# Power_Supply.net
KiCad netlist of a schematic drawn in Altium Designer
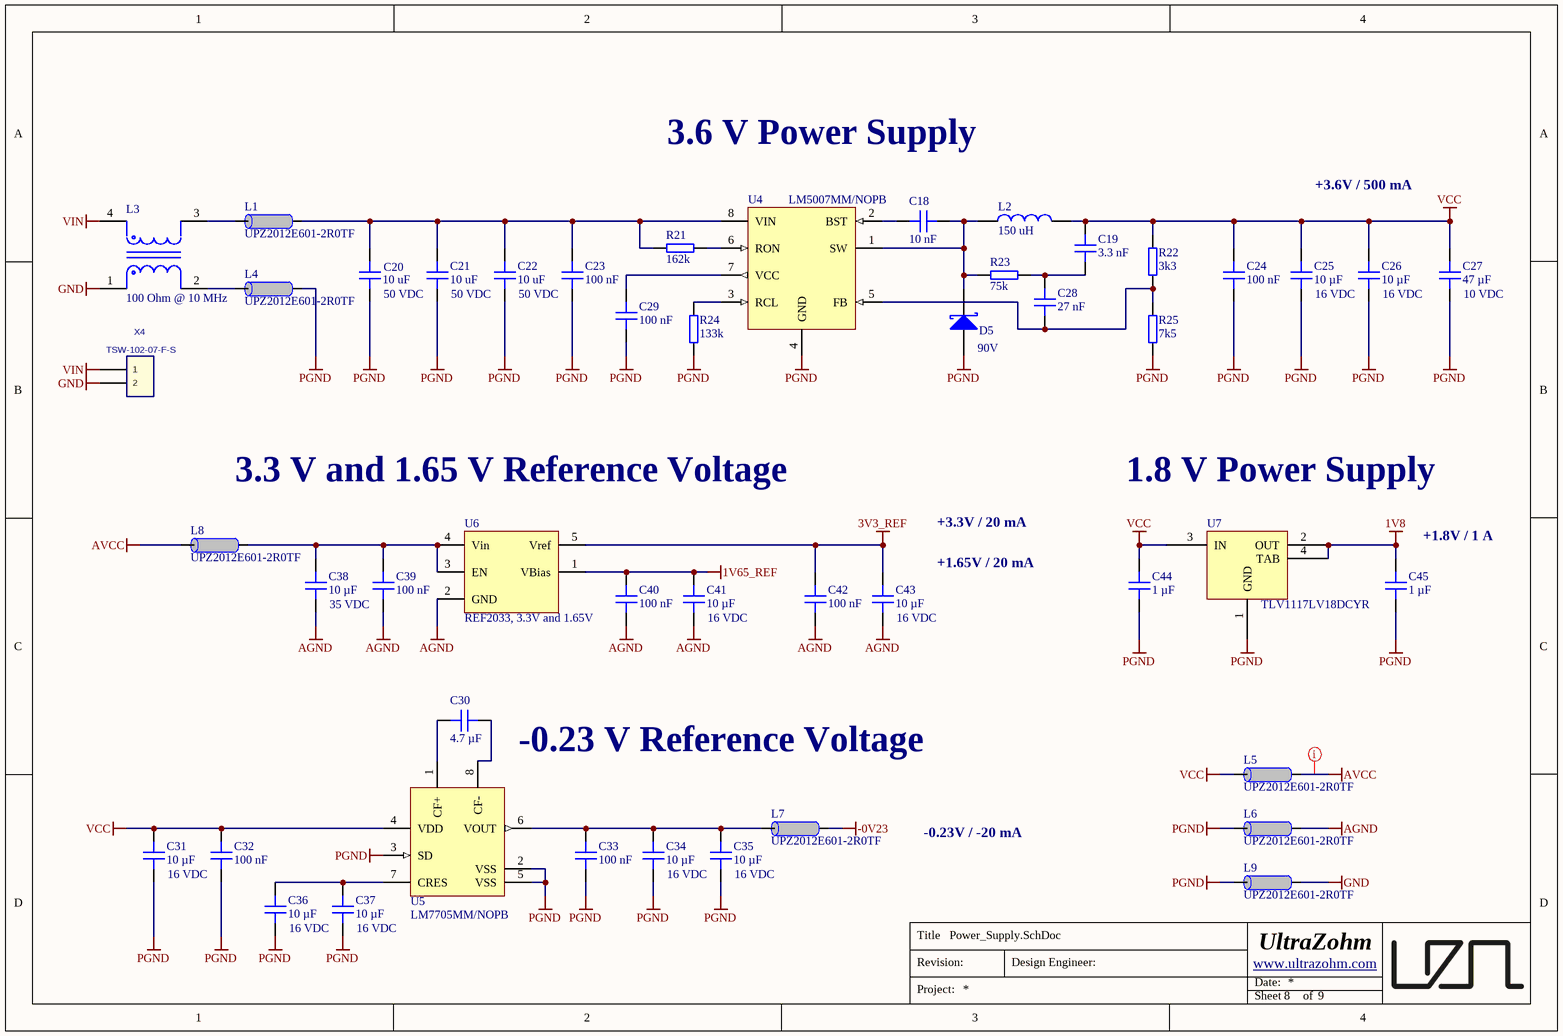
[diagram p0: Power_Supply.SchDoc]

(export (version "E")
  (design (tool "Eeschema 10.0.6"))
  (components
    (comp (ref "C18")
      (value "10 nF")
      (footprint "C_0603")
      (description "50V 10nF X7R ±10% 0603  Multilayer Ceramic Capacitors MLCC - SMD/SMT ROHS")
      (fields
        (field (name "MANUFACTURER PART NUMBER") "0603B103K500NT")
        (field (name "MANUFACTURER") "FH (Guangdong Fenghua Advanced Tech)")
        (field (name "CREATED FROM") "AGeiger")
      )
      (libsource (lib "user") (part "Capacitor"))
    )
    (comp (ref "C19")
      (value "3.3 nF")
      (footprint "C_0603")
      (description "50V 3.3nF X7R ±10% 0603  Multilayer Ceramic Capacitors MLCC - SMD/SMT ROHS")
      (fields
        (field (name "MANUFACTURER PART NUMBER") "CL10B332KB8NNNC")
        (field (name "MANUFACTURER") "Samsung Electro-Mechanics")
        (field (name "CREATED FROM") "AGeiger")
      )
      (libsource (lib "user") (part "Capacitor"))
    )
    (comp (ref "C20")
      (value "10 uF")
      (footprint "C_1206")
      (description "50V 10uF X7R ±10% 1206  Multilayer Ceramic Capacitors MLCC - SMD/SMT ROHS")
      (fields
        (field (name "MANUFACTURER PART NUMBER") "CL31B106KBHNNNE")
        (field (name "MANUFACTURER") "Samsung Electro-Mechanics")
        (field (name "VOLTAGE RATING") "50 VDC")
        (field (name "CREATED FROM") "AGeiger")
      )
      (libsource (lib "user") (part "Capacitor"))
    )
    (comp (ref "C21")
      (value "10 uF")
      (footprint "C_1206")
      (description "50V 10uF X7R ±10% 1206  Multilayer Ceramic Capacitors MLCC - SMD/SMT ROHS")
      (fields
        (field (name "MANUFACTURER PART NUMBER") "CL31B106KBHNNNE")
        (field (name "MANUFACTURER") "Samsung Electro-Mechanics")
        (field (name "VOLTAGE RATING") "50 VDC")
        (field (name "CREATED FROM") "AGeiger")
      )
      (libsource (lib "user") (part "Capacitor"))
    )
    (comp (ref "C22")
      (value "10 uF")
      (footprint "C_1206")
      (description "50V 10uF X7R ±10% 1206  Multilayer Ceramic Capacitors MLCC - SMD/SMT ROHS")
      (fields
        (field (name "MANUFACTURER PART NUMBER") "CL31B106KBHNNNE")
        (field (name "MANUFACTURER") "Samsung Electro-Mechanics")
        (field (name "VOLTAGE RATING") "50 VDC")
        (field (name "CREATED FROM") "AGeiger")
      )
      (libsource (lib "user") (part "Capacitor"))
    )
    (comp (ref "C23")
      (value "100 nF")
      (footprint "C_0603")
      (description "Capacitor 0603, 50 VDC, 100 nF, X7R")
      (fields
        (field (name "MANUFACTURER PART NUMBER") "CC0603KRX7R9BB104")
        (field (name "MANUFACTURER") "YAGEO")
        (field (name "CREATED FROM") "AGeiger")
      )
      (libsource (lib "user") (part "Capacitor"))
    )
    (comp (ref "C24")
      (value "100 nF")
      (footprint "C_0603")
      (description "Capacitor 0603, 50 VDC, 100 nF, X7R")
      (fields
        (field (name "MANUFACTURER PART NUMBER") "CC0603KRX7R9BB104")
        (field (name "MANUFACTURER") "YAGEO")
        (field (name "CREATED FROM") "AGeiger")
      )
      (libsource (lib "user") (part "Capacitor"))
    )
    (comp (ref "C25")
      (value "10 µF")
      (footprint "C_0603")
      (description "Capacitor 0603, 16 VDC, 10 µF, X5R")
      (fields
        (field (name "MANUFACTURER PART NUMBER") "CL10A106MO8NQNC")
        (field (name "MANUFACTURER") "Samsung Electro-Mechanics")
        (field (name "VOLTAGE RATING") "16 VDC")
        (field (name "CREATED FROM") "AGeiger")
      )
      (libsource (lib "user") (part "Capacitor"))
    )
    (comp (ref "C26")
      (value "10 µF")
      (footprint "C_0603")
      (description "Capacitor 0603, 16 VDC, 10 µF, X5R")
      (fields
        (field (name "MANUFACTURER PART NUMBER") "CL10A106MO8NQNC")
        (field (name "MANUFACTURER") "Samsung Electro-Mechanics")
        (field (name "VOLTAGE RATING") "16 VDC")
        (field (name "CREATED FROM") "AGeiger")
      )
      (libsource (lib "user") (part "Capacitor"))
    )
    (comp (ref "C27")
      (value "47 µF")
      (footprint "C_1210_N")
      (description "10V 47uF X7R ±10% 1210  Multilayer Ceramic Capacitors MLCC - SMD/SMT ROHS")
      (fields
        (field (name "MANUFACTURER PART NUMBER") "GRM32ER71A476KE15L")
        (field (name "MANUFACTURER") "Murata Electronics")
        (field (name "VOLTAGE RATING") "10 VDC")
        (field (name "CREATED FROM") "AGeiger")
      )
      (libsource (lib "user") (part "Capacitor"))
    )
    (comp (ref "C28")
      (value "27 nF")
      (footprint "C_0603")
      (description "50V 27nF X7R ±10% 0603  Multilayer Ceramic Capacitors MLCC - SMD/SMT ROHS")
      (fields
        (field (name "MANUFACTURER PART NUMBER") "CC0603KRX7R9BB273")
        (field (name "MANUFACTURER") "YAGEO")
        (field (name "CREATED FROM") "AGeiger")
      )
      (libsource (lib "user") (part "Capacitor"))
    )
    (comp (ref "C29")
      (value "100 nF")
      (footprint "C_0603")
      (description "Capacitor 0603, 50 VDC, 100 nF, X7R")
      (fields
        (field (name "MANUFACTURER PART NUMBER") "CC0603KRX7R9BB104")
        (field (name "MANUFACTURER") "YAGEO")
        (field (name "CREATED FROM") "AGeiger")
      )
      (libsource (lib "user") (part "Capacitor"))
    )
    (comp (ref "C30")
      (value "4.7 µF")
      (footprint "C_0805")
      (description "25V 4.7uF X5R ±10% 0805  Multilayer Ceramic Capacitors MLCC - SMD/SMT ROHS")
      (fields
        (field (name "MANUFACTURER PART NUMBER") "CL21A475KAQNNNE")
        (field (name "MANUFACTURER") "Samsung Electro-Mechanics")
        (field (name "CREATED FROM") "AGeiger")
      )
      (libsource (lib "user") (part "Capacitor"))
    )
    (comp (ref "C31")
      (value "10 µF")
      (footprint "C_0603")
      (description "Capacitor 0603, 16 VDC, 10 µF, X5R")
      (fields
        (field (name "MANUFACTURER PART NUMBER") "CL10A106MO8NQNC")
        (field (name "MANUFACTURER") "Samsung Electro-Mechanics")
        (field (name "VOLTAGE RATING") "16 VDC")
        (field (name "CREATED FROM") "AGeiger")
      )
      (libsource (lib "user") (part "Capacitor"))
    )
    (comp (ref "C32")
      (value "100 nF")
      (footprint "C_0603")
      (description "Capacitor 0603, 50 VDC, 100 nF, X7R")
      (fields
        (field (name "MANUFACTURER PART NUMBER") "CC0603KRX7R9BB104")
        (field (name "MANUFACTURER") "YAGEO")
        (field (name "CREATED FROM") "AGeiger")
      )
      (libsource (lib "user") (part "Capacitor"))
    )
    (comp (ref "C33")
      (value "100 nF")
      (footprint "C_0603")
      (description "Capacitor 0603, 50 VDC, 100 nF, X7R")
      (fields
        (field (name "MANUFACTURER PART NUMBER") "CC0603KRX7R9BB104")
        (field (name "MANUFACTURER") "YAGEO")
        (field (name "CREATED FROM") "AGeiger")
      )
      (libsource (lib "user") (part "Capacitor"))
    )
    (comp (ref "C34")
      (value "10 µF")
      (footprint "C_0603")
      (description "Capacitor 0603, 16 VDC, 10 µF, X5R")
      (fields
        (field (name "MANUFACTURER PART NUMBER") "CL10A106MO8NQNC")
        (field (name "MANUFACTURER") "Samsung Electro-Mechanics")
        (field (name "VOLTAGE RATING") "16 VDC")
        (field (name "CREATED FROM") "AGeiger")
      )
      (libsource (lib "user") (part "Capacitor"))
    )
    (comp (ref "C35")
      (value "10 µF")
      (footprint "C_0603")
      (description "Capacitor 0603, 16 VDC, 10 µF, X5R")
      (fields
        (field (name "MANUFACTURER PART NUMBER") "CL10A106MO8NQNC")
        (field (name "MANUFACTURER") "Samsung Electro-Mechanics")
        (field (name "VOLTAGE RATING") "16 VDC")
        (field (name "CREATED FROM") "AGeiger")
      )
      (libsource (lib "user") (part "Capacitor"))
    )
    (comp (ref "C36")
      (value "10 µF")
      (footprint "C_0603")
      (description "Capacitor 0603, 16 VDC, 10 µF, X5R")
      (fields
        (field (name "MANUFACTURER PART NUMBER") "CL10A106MO8NQNC")
        (field (name "MANUFACTURER") "Samsung Electro-Mechanics")
        (field (name "VOLTAGE RATING") "16 VDC")
        (field (name "CREATED FROM") "AGeiger")
      )
      (libsource (lib "user") (part "Capacitor"))
    )
    (comp (ref "C37")
      (value "10 µF")
      (footprint "C_0603")
      (description "Capacitor 0603, 16 VDC, 10 µF, X5R")
      (fields
        (field (name "MANUFACTURER PART NUMBER") "CL10A106MO8NQNC")
        (field (name "MANUFACTURER") "Samsung Electro-Mechanics")
        (field (name "VOLTAGE RATING") "16 VDC")
        (field (name "CREATED FROM") "AGeiger")
      )
      (libsource (lib "user") (part "Capacitor"))
    )
    (comp (ref "C38")
      (value "10 µF")
      (footprint "CAPC_0805_L")
      (description "Capacitor 0805, 35 VDC, 10 µF, X5R")
      (fields
        (field (name "MANUFACTURER PART NUMBER") "GRM21BR6YA106KE43L")
        (field (name "MANUFACTURER") "Murata Electronics")
        (field (name "VOLTAGE RATING") "35 VDC")
        (field (name "CREATED FROM") "AGeiger")
      )
      (libsource (lib "user") (part "Capacitor"))
    )
    (comp (ref "C39")
      (value "100 nF")
      (footprint "C_0603")
      (description "Capacitor 0603, 50 VDC, 100 nF, X7R")
      (fields
        (field (name "MANUFACTURER PART NUMBER") "CC0603KRX7R9BB104")
        (field (name "MANUFACTURER") "YAGEO")
        (field (name "CREATED FROM") "AGeiger")
      )
      (libsource (lib "user") (part "Capacitor"))
    )
    (comp (ref "C40")
      (value "100 nF")
      (footprint "C_0603")
      (description "Capacitor 0603, 50 VDC, 100 nF, X7R")
      (fields
        (field (name "MANUFACTURER PART NUMBER") "CC0603KRX7R9BB104")
        (field (name "MANUFACTURER") "YAGEO")
        (field (name "CREATED FROM") "AGeiger")
      )
      (libsource (lib "user") (part "Capacitor"))
    )
    (comp (ref "C41")
      (value "10 µF")
      (footprint "C_0603")
      (description "Capacitor 0603, 16 VDC, 10 µF, X5R")
      (fields
        (field (name "MANUFACTURER PART NUMBER") "CL10A106MO8NQNC")
        (field (name "MANUFACTURER") "Samsung Electro-Mechanics")
        (field (name "VOLTAGE RATING") "16 VDC")
        (field (name "CREATED FROM") "AGeiger")
      )
      (libsource (lib "user") (part "Capacitor"))
    )
    (comp (ref "C42")
      (value "100 nF")
      (footprint "C_0603")
      (description "Capacitor 0603, 50 VDC, 100 nF, X7R")
      (fields
        (field (name "MANUFACTURER PART NUMBER") "CC0603KRX7R9BB104")
        (field (name "MANUFACTURER") "YAGEO")
        (field (name "CREATED FROM") "AGeiger")
      )
      (libsource (lib "user") (part "Capacitor"))
    )
    (comp (ref "C43")
      (value "10 µF")
      (footprint "C_0603")
      (description "Capacitor 0603, 16 VDC, 10 µF, X5R")
      (fields
        (field (name "MANUFACTURER PART NUMBER") "CL10A106MO8NQNC")
        (field (name "MANUFACTURER") "Samsung Electro-Mechanics")
        (field (name "VOLTAGE RATING") "16 VDC")
        (field (name "CREATED FROM") "AGeiger")
      )
      (libsource (lib "user") (part "Capacitor"))
    )
    (comp (ref "C44")
      (value "1 µF")
      (footprint "C_0603")
      (description "50V 1uF X7R ±10% 0603 Multilayer Ceramic Capacitors MLCC - SMD/SMT ROHS")
      (fields
        (field (name "MANUFACTURER PART NUMBER") "UMK107AB7105KA-T")
        (field (name "MANUFACTURER") "Taiyo Yuden")
        (field (name "CREATED FROM") "NDiringer")
      )
      (libsource (lib "user") (part "Capacitor"))
    )
    (comp (ref "C45")
      (value "1 µF")
      (footprint "C_0603")
      (description "50V 1uF X7R ±10% 0603 Multilayer Ceramic Capacitors MLCC - SMD/SMT ROHS")
      (fields
        (field (name "MANUFACTURER PART NUMBER") "UMK107AB7105KA-T")
        (field (name "MANUFACTURER") "Taiyo Yuden")
        (field (name "CREATED FROM") "NDiringer")
      )
      (libsource (lib "user") (part "Capacitor"))
    )
    (comp (ref "D5")
      (value "90V")
      (footprint "DIOM5226X262N")
      (description "Schottky Diode, 90 V, 3 A")
      (fields
        (field (name "MF") "Vishay")
        (field (name "MPN") "BYS12-90-E3/TR3")
        (field (name "CREATED FROM") "AGeiger")
      )
      (libsource (lib "user") (part "BYS12-90"))
    )
    (comp (ref "L1")
      (value "UPZ2012E601-2R0TF")
      (footprint "INDC2012X92N_V")
      (description "2A 1 90mΩ 600Ω@100MHz ±25% 0805  Ferrite Beads ROHS")
      (fields
        (field (name "MANUFACTURER") "Sunlord")
        (field (name "LCSC PART NUMBER") "C98308")
        (field (name "CREATED FROM") "AGeiger")
      )
      (libsource (lib "user") (part "Ferrite_Bead"))
    )
    (comp (ref "L2")
      (value "150 uH")
      (footprint "POWER_INDUCTOR_8040")
      (description "850mA 150uH ±20% 410mΩ SMD  Power Inductors ROHS")
      (fields
        (field (name "MF") "EPCOS / TDK")
        (field (name "MPN") "B82464G4154M")
        (field (name "CREATED FROM") "AGeiger")
      )
      (libsource (lib "user") (part "B82464G4154M"))
    )
    (comp (ref "L3")
      (value "100 Ohm @ 10 MHz")
      (footprint "FP-DLW5BT-MFG")
      (description "-40℃~125℃ 1.5A 56mΩ 50V 100Ω @ 10MHz 125VDC SMD,5x5mm Common Mode Filters ROHS")
      (fields
        (field (name "MANUFACTURER PART NUMBER") "DLW5BTH142TQ2L")
        (field (name "MANUFACTURER") "Murata")
        (field (name "CREATED FROM") "AGeiger")
      )
      (libsource (lib "user") (part "Common_Mode_Filter"))
    )
    (comp (ref "L4")
      (value "UPZ2012E601-2R0TF")
      (footprint "INDC2012X92N_V")
      (description "2A 1 90mΩ 600Ω@100MHz ±25% 0805  Ferrite Beads ROHS")
      (fields
        (field (name "MANUFACTURER") "Sunlord")
        (field (name "LCSC PART NUMBER") "C98308")
        (field (name "CREATED FROM") "AGeiger")
      )
      (libsource (lib "user") (part "Ferrite_Bead"))
    )
    (comp (ref "L5")
      (value "UPZ2012E601-2R0TF")
      (footprint "INDC2012X92N_V")
      (description "2A 1 90mΩ 600Ω@100MHz ±25% 0805  Ferrite Beads ROHS")
      (fields
        (field (name "MANUFACTURER") "Sunlord")
        (field (name "LCSC PART NUMBER") "C98308")
        (field (name "CREATED FROM") "AGeiger")
      )
      (libsource (lib "user") (part "Ferrite_Bead"))
    )
    (comp (ref "L6")
      (value "UPZ2012E601-2R0TF")
      (footprint "INDC2012X92N_V")
      (description "2A 1 90mΩ 600Ω@100MHz ±25% 0805  Ferrite Beads ROHS")
      (fields
        (field (name "MANUFACTURER") "Sunlord")
        (field (name "LCSC PART NUMBER") "C98308")
        (field (name "CREATED FROM") "AGeiger")
      )
      (libsource (lib "user") (part "Ferrite_Bead"))
    )
    (comp (ref "L7")
      (value "UPZ2012E601-2R0TF")
      (footprint "INDC2012X92N_V")
      (description "2A 1 90mΩ 600Ω@100MHz ±25% 0805  Ferrite Beads ROHS")
      (fields
        (field (name "MANUFACTURER") "Sunlord")
        (field (name "LCSC PART NUMBER") "C98308")
        (field (name "CREATED FROM") "AGeiger")
      )
      (libsource (lib "user") (part "Ferrite_Bead"))
    )
    (comp (ref "L8")
      (value "UPZ2012E601-2R0TF")
      (footprint "INDC2012X92N_V")
      (description "2A 1 90mΩ 600Ω@100MHz ±25% 0805  Ferrite Beads ROHS")
      (fields
        (field (name "MANUFACTURER") "Sunlord")
        (field (name "LCSC PART NUMBER") "C98308")
        (field (name "CREATED FROM") "AGeiger")
      )
      (libsource (lib "user") (part "Ferrite_Bead"))
    )
    (comp (ref "L9")
      (value "UPZ2012E601-2R0TF")
      (footprint "INDC2012X92N_V")
      (description "2A 1 90mΩ 600Ω@100MHz ±25% 0805  Ferrite Beads ROHS")
      (fields
        (field (name "MANUFACTURER") "Sunlord")
        (field (name "LCSC PART NUMBER") "C98308")
        (field (name "CREATED FROM") "AGeiger")
      )
      (libsource (lib "user") (part "Ferrite_Bead"))
    )
    (comp (ref "R21")
      (value "162k")
      (footprint "RES 0603_1608")
      (fields
        (field (name "MANUFACTURER PART NUMBER") "0603WAF1623T5E")
        (field (name "MANUFACTURER") "UNI-ROYAL")
        (field (name "TOLERANCE") "1%")
        (field (name "CREATED FROM") "AGeiger")
      )
      (libsource (lib "user") (part "Resistor"))
    )
    (comp (ref "R22")
      (value "3k3")
      (footprint "RES 0603_1608")
      (fields
        (field (name "MANUFACTURER PART NUMBER") "0603WAF3301T5E")
        (field (name "MANUFACTURER") "UNI-ROYAL")
        (field (name "TOLERANCE") "1%")
        (field (name "CREATED FROM") "AGeiger")
      )
      (libsource (lib "user") (part "Resistor"))
    )
    (comp (ref "R23")
      (value "75k")
      (footprint "RES 0603_1608")
      (fields
        (field (name "MANUFACTURER PART NUMBER") "0603WAF7502T5E")
        (field (name "MANUFACTURER") "UNI-ROYAL")
        (field (name "TOLERANCE") "1%")
        (field (name "CREATED FROM") "AGeiger")
      )
      (libsource (lib "user") (part "Resistor"))
    )
    (comp (ref "R24")
      (value "133k")
      (footprint "RES 0603_1608")
      (fields
        (field (name "MANUFACTURER PART NUMBER") "AC0603FR-07133KL")
        (field (name "MANUFACTURER") "YAGEO")
        (field (name "TOLERANCE") "1%")
        (field (name "CREATED FROM") "AGeiger")
      )
      (libsource (lib "user") (part "Resistor"))
    )
    (comp (ref "R25")
      (value "7k5")
      (footprint "RES 0603_1608")
      (fields
        (field (name "MANUFACTURER PART NUMBER") "0603WAF7501T5E")
        (field (name "MANUFACTURER") "UNI-ROYAL")
        (field (name "TOLERANCE") "1%")
        (field (name "CREATED FROM") "AGeiger")
      )
      (libsource (lib "user") (part "Resistor"))
    )
    (comp (ref "U4")
      (value "LM5007MM/NOPB")
      (footprint "TSOP65P490X110-8N")
      (fields
        (field (name "MANUFACTURER") "Texas Instruments")
        (field (name "LCSC PART NUMBER") "C23920")
        (field (name "CREATED FROM") "AGeiger")
      )
      (libsource (lib "user") (part "LM5007"))
    )
    (comp (ref "U5")
      (value "LM7705MM/NOPB")
      (footprint "MSOP-8_DGK0008A_L")
      (description "Low-Noise Negative Bias Generator")
      (fields
        (field (name "MF") "Texas Instruments")
        (field (name "LCSC PART NUMBER") "C129980")
        (field (name "CREATED FROM") "AGeiger")
      )
      (libsource (lib "user") (part "LM7705"))
    )
    (comp (ref "U6")
      (value "REF2033, 3.3V and 1.65V")
      (footprint "SOT23-5_N")
      (description "REF20xx Low-Drift, Low-Power, Dual-Output, VREF and VREF / 2 Voltage References")
      (fields
        (field (name "MANUFACTURER PART NUMBER") "REF2033AIDDCT")
        (field (name "MANUFACTURER") "Texas Instruments")
        (field (name "CREATED FROM") "AGeiger")
      )
      (libsource (lib "user") (part "REF2033"))
    )
    (comp (ref "U7")
      (value "TLV1117LV18DCYR")
      (footprint "SOT230P700X170-4N")
      (description "1-A, Positive Fixed-Voltage, Low-Dropout Regulator")
      (fields
        (field (name "MF") "Texas Instruments")
        (field (name "LCSC PART NUMBER") "C80105")
        (field (name "CREATED FROM") "AGeiger")
      )
      (libsource (lib "user") (part "TLV1117LV18DCYR"))
    )
    (comp (ref "X4")
      (value "TSW-102-07-F-S")
      (footprint "TSW-102-XX-XXX-S")
      (description "Pin Header, 2.54mm, 2x1")
      (fields
        (field (name "MANUFACTURER") "SAMTEC")
        (field (name "CREATED BY") "May 18, 2016 - Wendy Xin")
        (field (name "CREATED FROM") "AGeiger")
      )
      (libsource (lib "user") (part "TSW-102-XX-XXX-S"))
    )
  )
  (nets
    (net (code "1") (name "-0V23") (class "Default")
      (node (ref "L7") (pin "1") (pinfunction "1_1") (pintype "passive"))
    )
    (net (code "2") (name "1V8") (class "Default")
      (node (ref "C45") (pin "2") (pinfunction "2_2") (pintype "passive"))
      (node (ref "U7") (pin "2") (pinfunction "OUT_2") (pintype "power_in"))
      (node (ref "U7") (pin "4") (pinfunction "TAB_4") (pintype "power_in"))
    )
    (net (code "3") (name "1V65_REF") (class "Default")
      (node (ref "C40") (pin "2") (pinfunction "2_2") (pintype "passive"))
      (node (ref "C41") (pin "2") (pinfunction "2_2") (pintype "passive"))
      (node (ref "U6") (pin "1") (pinfunction "VBias_1") (pintype "passive"))
    )
    (net (code "4") (name "3V3_REF") (class "Default")
      (node (ref "C42") (pin "2") (pinfunction "2_2") (pintype "passive"))
      (node (ref "C43") (pin "2") (pinfunction "2_2") (pintype "passive"))
      (node (ref "U6") (pin "5") (pinfunction "Vref_5") (pintype "passive"))
    )
    (net (code "5") (name "AGND") (class "Default")
      (node (ref "C38") (pin "1") (pinfunction "1_1") (pintype "passive"))
      (node (ref "C39") (pin "1") (pinfunction "1_1") (pintype "passive"))
      (node (ref "C40") (pin "1") (pinfunction "1_1") (pintype "passive"))
      (node (ref "C41") (pin "1") (pinfunction "1_1") (pintype "passive"))
      (node (ref "C42") (pin "1") (pinfunction "1_1") (pintype "passive"))
      (node (ref "C43") (pin "1") (pinfunction "1_1") (pintype "passive"))
      (node (ref "L6") (pin "1") (pinfunction "1_1") (pintype "passive"))
      (node (ref "U6") (pin "2") (pinfunction "GND_2") (pintype "passive"))
    )
    (net (code "6") (name "AVCC") (class "Default")
      (node (ref "L5") (pin "1") (pinfunction "1_1") (pintype "passive"))
      (node (ref "L8") (pin "2") (pinfunction "2_2") (pintype "passive"))
    )
    (net (code "7") (name "GND") (class "Default")
      (node (ref "L3") (pin "1") (pinfunction "1_1") (pintype "passive"))
      (node (ref "L9") (pin "1") (pinfunction "1_1") (pintype "passive"))
      (node (ref "X4") (pin "2") (pinfunction "2_2") (pintype "passive"))
    )
    (net (code "8") (name "Net-(C19-Pad1)") (class "Default")
      (node (ref "C19") (pin "1") (pinfunction "1_1") (pintype "passive"))
      (node (ref "C28") (pin "2") (pinfunction "2_2") (pintype "passive"))
      (node (ref "R23") (pin "2") (pinfunction "2_2") (pintype "passive"))
    )
    (net (code "9") (name "Net-(D5-K)") (class "Default")
      (node (ref "C18") (pin "2") (pinfunction "2_2") (pintype "passive"))
      (node (ref "D5") (pin "1") (pinfunction "K_1") (pintype "passive"))
      (node (ref "L2") (pin "1") (pinfunction "1_1") (pintype "passive"))
      (node (ref "R23") (pin "1") (pinfunction "1_1") (pintype "passive"))
      (node (ref "U4") (pin "1") (pinfunction "SW_1") (pintype "power_in"))
    )
    (net (code "10") (name "Net-(L1-Pad2)") (class "Default")
      (node (ref "L1") (pin "2") (pinfunction "2_2") (pintype "passive"))
      (node (ref "L3") (pin "3") (pinfunction "3_3") (pintype "passive"))
    )
    (net (code "11") (name "Net-(L3-Pad2)") (class "Default")
      (node (ref "L3") (pin "2") (pinfunction "2_2") (pintype "passive"))
      (node (ref "L4") (pin "2") (pinfunction "2_2") (pintype "passive"))
    )
    (net (code "12") (name "Net-(U4-BST)") (class "Default")
      (node (ref "C18") (pin "1") (pinfunction "1_1") (pintype "passive"))
      (node (ref "U4") (pin "2") (pinfunction "BST_2") (pintype "input"))
    )
    (net (code "13") (name "Net-(U4-FB)") (class "Default")
      (node (ref "C28") (pin "1") (pinfunction "1_1") (pintype "passive"))
      (node (ref "R22") (pin "1") (pinfunction "1_1") (pintype "passive"))
      (node (ref "R25") (pin "2") (pinfunction "2_2") (pintype "passive"))
      (node (ref "U4") (pin "5") (pinfunction "FB_5") (pintype "input"))
    )
    (net (code "14") (name "Net-(U4-RCL)") (class "Default")
      (node (ref "R24") (pin "2") (pinfunction "2_2") (pintype "passive"))
      (node (ref "U4") (pin "3") (pinfunction "RCL_3") (pintype "input"))
    )
    (net (code "15") (name "Net-(U4-RON)") (class "Default")
      (node (ref "R21") (pin "2") (pinfunction "2_2") (pintype "passive"))
      (node (ref "U4") (pin "6") (pinfunction "RON_6") (pintype "input"))
    )
    (net (code "16") (name "Net-(U4-VCC)") (class "Default")
      (node (ref "C29") (pin "2") (pinfunction "2_2") (pintype "passive"))
      (node (ref "U4") (pin "7") (pinfunction "VCC_7") (pintype "output"))
    )
    (net (code "17") (name "Net-(U4-VIN)") (class "Default")
      (node (ref "C20") (pin "2") (pinfunction "2_2") (pintype "passive"))
      (node (ref "C21") (pin "2") (pinfunction "2_2") (pintype "passive"))
      (node (ref "C22") (pin "2") (pinfunction "2_2") (pintype "passive"))
      (node (ref "C23") (pin "2") (pinfunction "2_2") (pintype "passive"))
      (node (ref "L1") (pin "1") (pinfunction "1_1") (pintype "passive"))
      (node (ref "R21") (pin "1") (pinfunction "1_1") (pintype "passive"))
      (node (ref "U4") (pin "8") (pinfunction "VIN_8") (pintype "power_in"))
    )
    (net (code "18") (name "Net-(U5-CF+)") (class "Default")
      (node (ref "C30") (pin "1") (pinfunction "1_1") (pintype "passive"))
      (node (ref "U5") (pin "1") (pinfunction "CF+_1") (pintype "passive"))
    )
    (net (code "19") (name "Net-(U5-CF-)") (class "Default")
      (node (ref "C30") (pin "2") (pinfunction "2_2") (pintype "passive"))
      (node (ref "U5") (pin "8") (pinfunction "CF-_8") (pintype "passive"))
    )
    (net (code "20") (name "Net-(U5-CRES)") (class "Default")
      (node (ref "C36") (pin "2") (pinfunction "2_2") (pintype "passive"))
      (node (ref "C37") (pin "2") (pinfunction "2_2") (pintype "passive"))
      (node (ref "U5") (pin "7") (pinfunction "CRES_7") (pintype "passive"))
    )
    (net (code "21") (name "Net-(U5-VOUT)") (class "Default")
      (node (ref "C33") (pin "2") (pinfunction "2_2") (pintype "passive"))
      (node (ref "C34") (pin "2") (pinfunction "2_2") (pintype "passive"))
      (node (ref "C35") (pin "2") (pinfunction "2_2") (pintype "passive"))
      (node (ref "L7") (pin "2") (pinfunction "2_2") (pintype "passive"))
      (node (ref "U5") (pin "6") (pinfunction "VOUT_6") (pintype "output"))
    )
    (net (code "22") (name "Net-(U6-EN)") (class "Default")
      (node (ref "C38") (pin "2") (pinfunction "2_2") (pintype "passive"))
      (node (ref "C39") (pin "2") (pinfunction "2_2") (pintype "passive"))
      (node (ref "L8") (pin "1") (pinfunction "1_1") (pintype "passive"))
      (node (ref "U6") (pin "3") (pinfunction "EN_3") (pintype "passive"))
      (node (ref "U6") (pin "4") (pinfunction "Vin_4") (pintype "passive"))
    )
    (net (code "23") (name "PGND") (class "Default")
      (node (ref "C20") (pin "1") (pinfunction "1_1") (pintype "passive"))
      (node (ref "C21") (pin "1") (pinfunction "1_1") (pintype "passive"))
      (node (ref "C22") (pin "1") (pinfunction "1_1") (pintype "passive"))
      (node (ref "C23") (pin "1") (pinfunction "1_1") (pintype "passive"))
      (node (ref "C24") (pin "1") (pinfunction "1_1") (pintype "passive"))
      (node (ref "C25") (pin "1") (pinfunction "1_1") (pintype "passive"))
      (node (ref "C26") (pin "1") (pinfunction "1_1") (pintype "passive"))
      (node (ref "C27") (pin "1") (pinfunction "1_1") (pintype "passive"))
      (node (ref "C29") (pin "1") (pinfunction "1_1") (pintype "passive"))
      (node (ref "C31") (pin "1") (pinfunction "1_1") (pintype "passive"))
      (node (ref "C32") (pin "1") (pinfunction "1_1") (pintype "passive"))
      (node (ref "C33") (pin "1") (pinfunction "1_1") (pintype "passive"))
      (node (ref "C34") (pin "1") (pinfunction "1_1") (pintype "passive"))
      (node (ref "C35") (pin "1") (pinfunction "1_1") (pintype "passive"))
      (node (ref "C36") (pin "1") (pinfunction "1_1") (pintype "passive"))
      (node (ref "C37") (pin "1") (pinfunction "1_1") (pintype "passive"))
      (node (ref "C44") (pin "1") (pinfunction "1_1") (pintype "passive"))
      (node (ref "C45") (pin "1") (pinfunction "1_1") (pintype "passive"))
      (node (ref "D5") (pin "2") (pinfunction "A_2") (pintype "passive"))
      (node (ref "L4") (pin "1") (pinfunction "1_1") (pintype "passive"))
      (node (ref "L6") (pin "2") (pinfunction "2_2") (pintype "passive"))
      (node (ref "L9") (pin "2") (pinfunction "2_2") (pintype "passive"))
      (node (ref "R24") (pin "1") (pinfunction "1_1") (pintype "passive"))
      (node (ref "R25") (pin "1") (pinfunction "1_1") (pintype "passive"))
      (node (ref "U4") (pin "4") (pinfunction "GND_4") (pintype "power_in"))
      (node (ref "U5") (pin "2") (pinfunction "VSS_2") (pintype "power_in"))
      (node (ref "U5") (pin "3") (pinfunction "SD_3") (pintype "input"))
      (node (ref "U5") (pin "5") (pinfunction "VSS_5") (pintype "power_in"))
      (node (ref "U7") (pin "1") (pinfunction "GND_1") (pintype "power_in"))
    )
    (net (code "24") (name "VCC") (class "Default")
      (node (ref "C19") (pin "2") (pinfunction "2_2") (pintype "passive"))
      (node (ref "C24") (pin "2") (pinfunction "2_2") (pintype "passive"))
      (node (ref "C25") (pin "2") (pinfunction "2_2") (pintype "passive"))
      (node (ref "C26") (pin "2") (pinfunction "2_2") (pintype "passive"))
      (node (ref "C27") (pin "2") (pinfunction "2_2") (pintype "passive"))
      (node (ref "C31") (pin "2") (pinfunction "2_2") (pintype "passive"))
      (node (ref "C32") (pin "2") (pinfunction "2_2") (pintype "passive"))
      (node (ref "C44") (pin "2") (pinfunction "2_2") (pintype "passive"))
      (node (ref "L2") (pin "2") (pinfunction "2_2") (pintype "passive"))
      (node (ref "L5") (pin "2") (pinfunction "2_2") (pintype "passive"))
      (node (ref "R22") (pin "2") (pinfunction "2_2") (pintype "passive"))
      (node (ref "U5") (pin "4") (pinfunction "VDD_4") (pintype "power_in"))
      (node (ref "U7") (pin "3") (pinfunction "IN_3") (pintype "power_in"))
    )
    (net (code "25") (name "VIN") (class "Default")
      (node (ref "L3") (pin "4") (pinfunction "4_4") (pintype "passive"))
      (node (ref "X4") (pin "1") (pinfunction "1_1") (pintype "passive"))
    )
  )
)
